# I2C_MULTIPLEX.net
KiCad netlist of a schematic drawn in Altium Designer
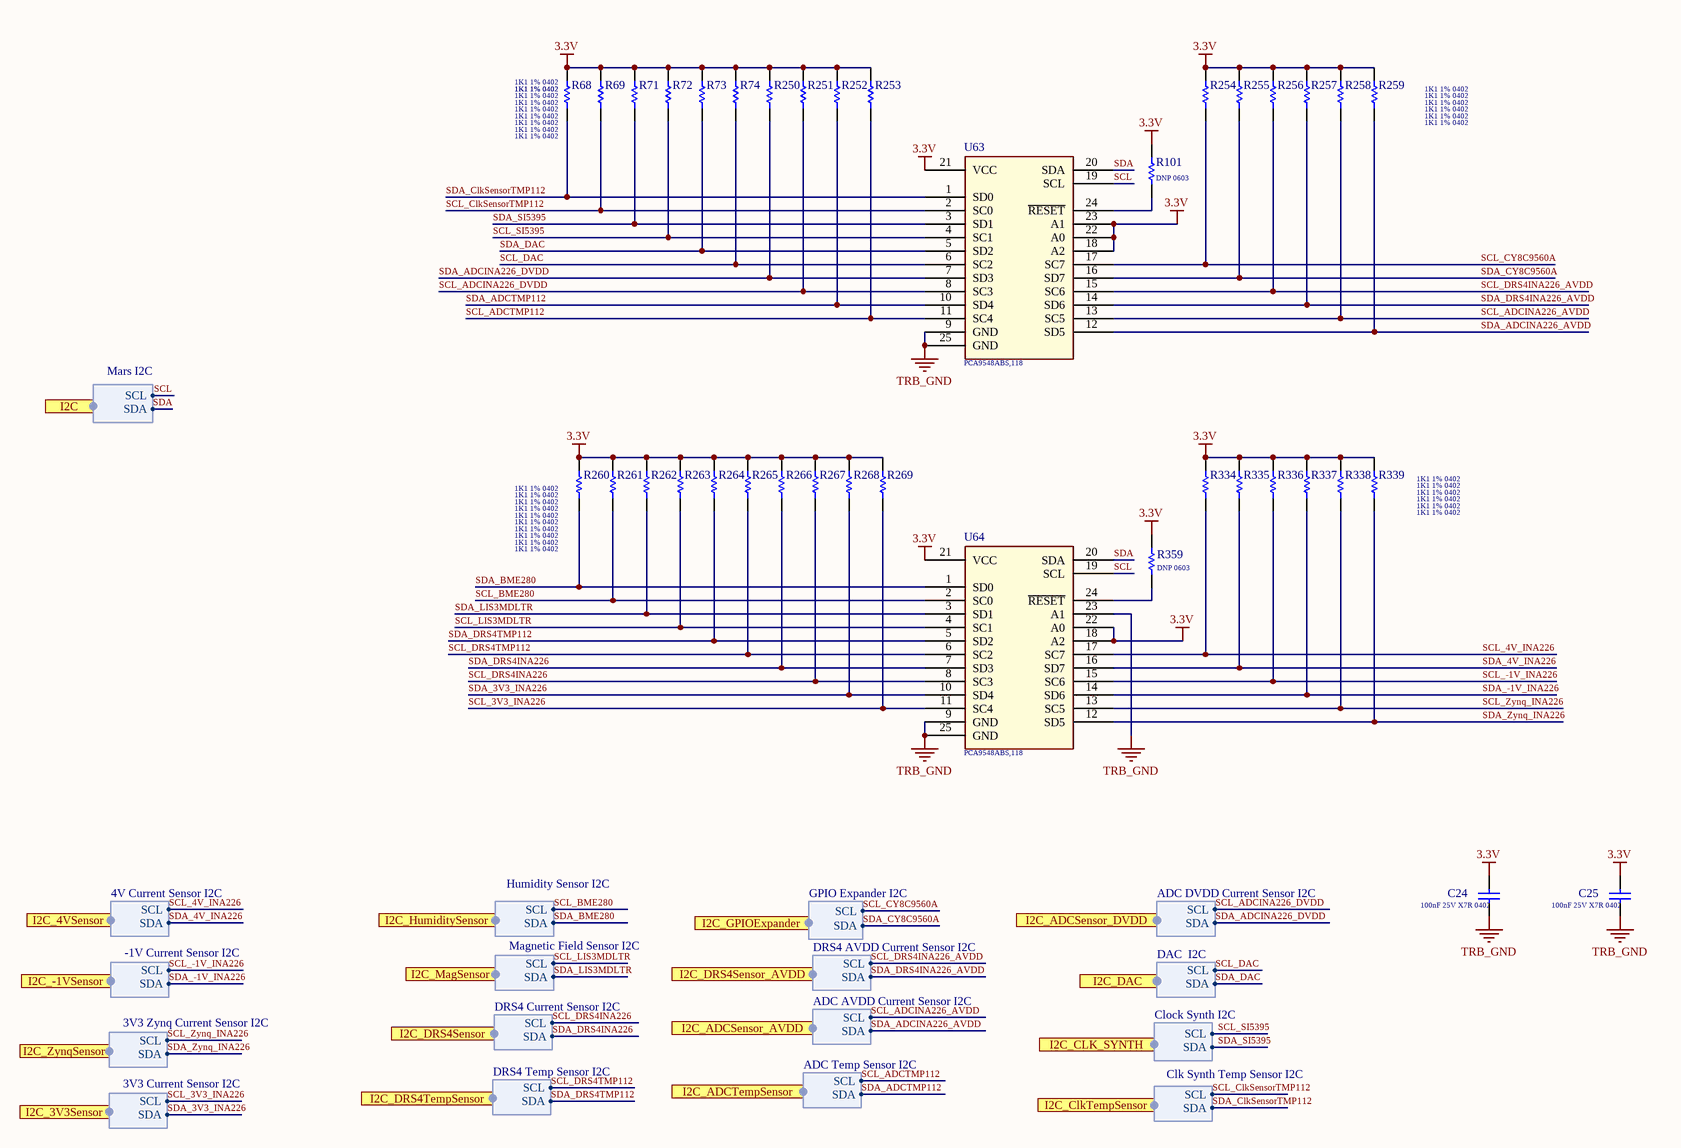
[diagram p0: I2C_MULTIPLEX.SchDoc]

(export (version "E")
  (design (tool "Eeschema 10.0.6"))
  (components
    (comp (ref "C24")
      (value "Cap_Taiyo_Yuden_TMK105B7104KV-FR_100nF")
      (footprint "Cap_Taiyo_Yuden_TMK105B7104KV-FR_100nF")
      (description "CAP CER 100nF 25V X7R 0402")
      (fields (field (name "CAPACITANCE") "100nF 25V X7R 0402"))
      (libsource (lib "Cap_Taiyo_Yuden_TMK105B7104KV-FR_100nF") (part "Cap_Taiyo_Yuden_TMK105B7104KV-FR_100nF"))
    )
    (comp (ref "C25")
      (value "Cap_Taiyo_Yuden_TMK105B7104KV-FR_100nF")
      (footprint "Cap_Taiyo_Yuden_TMK105B7104KV-FR_100nF")
      (description "CAP CER 100nF 25V X7R 0402")
      (fields (field (name "CAPACITANCE") "100nF 25V X7R 0402"))
      (libsource (lib "Cap_Taiyo_Yuden_TMK105B7104KV-FR_100nF") (part "Cap_Taiyo_Yuden_TMK105B7104KV-FR_100nF"))
    )
    (comp (ref "R68")
      (value "1K1 1% 0402")
      (footprint "RESC0402(1005)_L")
      (description "1K1 0.063W 1% 0402 (1005 Metric)  SMD")
      (fields (field (name "POWER") "0.063 W") (field (name "TOLERANCE") "1 %"))
      (libsource (lib "Altium Content Vault") (part "RES"))
    )
    (comp (ref "R69")
      (value "1K1 1% 0402")
      (footprint "RESC0402(1005)_L")
      (description "1K1 0.063W 1% 0402 (1005 Metric)  SMD")
      (fields (field (name "POWER") "0.063 W") (field (name "TOLERANCE") "1 %"))
      (libsource (lib "Altium Content Vault") (part "RES"))
    )
    (comp (ref "R71")
      (value "1K1 1% 0402")
      (footprint "RESC0402(1005)_L")
      (description "1K1 0.063W 1% 0402 (1005 Metric)  SMD")
      (fields (field (name "POWER") "0.063 W") (field (name "TOLERANCE") "1 %"))
      (libsource (lib "Altium Content Vault") (part "RES"))
    )
    (comp (ref "R72")
      (value "1K1 1% 0402")
      (footprint "RESC0402(1005)_L")
      (description "1K1 0.063W 1% 0402 (1005 Metric)  SMD")
      (fields (field (name "POWER") "0.063 W") (field (name "TOLERANCE") "1 %"))
      (libsource (lib "Altium Content Vault") (part "RES"))
    )
    (comp (ref "R73")
      (value "1K1 1% 0402")
      (footprint "RESC0402(1005)_L")
      (description "1K1 0.063W 1% 0402 (1005 Metric)  SMD")
      (fields (field (name "POWER") "0.063 W") (field (name "TOLERANCE") "1 %"))
      (libsource (lib "Altium Content Vault") (part "RES"))
    )
    (comp (ref "R74")
      (value "1K1 1% 0402")
      (footprint "RESC0402(1005)_L")
      (description "1K1 0.063W 1% 0402 (1005 Metric)  SMD")
      (fields (field (name "POWER") "0.063 W") (field (name "TOLERANCE") "1 %"))
      (libsource (lib "Altium Content Vault") (part "RES"))
    )
    (comp (ref "R101")
      (value "RES_DNP_0603")
      (footprint "RES_DNP_0603")
      (description "0603 Do not place resistor")
      (fields (field (name "RESISTANCE") "DNP 0603"))
      (libsource (lib "RES_DNP_0603") (part "RES_DNP_0603"))
    )
    (comp (ref "R250")
      (value "1K1 1% 0402")
      (footprint "RESC0402(1005)_L")
      (description "1K1 0.063W 1% 0402 (1005 Metric)  SMD")
      (fields (field (name "POWER") "0.063 W") (field (name "TOLERANCE") "1 %"))
      (libsource (lib "Altium Content Vault") (part "RES"))
    )
    (comp (ref "R251")
      (value "1K1 1% 0402")
      (footprint "RESC0402(1005)_L")
      (description "1K1 0.063W 1% 0402 (1005 Metric)  SMD")
      (fields (field (name "POWER") "0.063 W") (field (name "TOLERANCE") "1 %"))
      (libsource (lib "Altium Content Vault") (part "RES"))
    )
    (comp (ref "R252")
      (value "1K1 1% 0402")
      (footprint "RESC0402(1005)_L")
      (description "1K1 0.063W 1% 0402 (1005 Metric)  SMD")
      (fields (field (name "POWER") "0.063 W") (field (name "TOLERANCE") "1 %"))
      (libsource (lib "Altium Content Vault") (part "RES"))
    )
    (comp (ref "R253")
      (value "1K1 1% 0402")
      (footprint "RESC0402(1005)_L")
      (description "1K1 0.063W 1% 0402 (1005 Metric)  SMD")
      (fields (field (name "POWER") "0.063 W") (field (name "TOLERANCE") "1 %"))
      (libsource (lib "Altium Content Vault") (part "RES"))
    )
    (comp (ref "R254")
      (value "1K1 1% 0402")
      (footprint "RESC0402(1005)_L")
      (description "1K1 0.063W 1% 0402 (1005 Metric)  SMD")
      (fields (field (name "POWER") "0.063 W") (field (name "TOLERANCE") "1 %"))
      (libsource (lib "Altium Content Vault") (part "RES"))
    )
    (comp (ref "R255")
      (value "1K1 1% 0402")
      (footprint "RESC0402(1005)_L")
      (description "1K1 0.063W 1% 0402 (1005 Metric)  SMD")
      (fields (field (name "POWER") "0.063 W") (field (name "TOLERANCE") "1 %"))
      (libsource (lib "Altium Content Vault") (part "RES"))
    )
    (comp (ref "R256")
      (value "1K1 1% 0402")
      (footprint "RESC0402(1005)_L")
      (description "1K1 0.063W 1% 0402 (1005 Metric)  SMD")
      (fields (field (name "POWER") "0.063 W") (field (name "TOLERANCE") "1 %"))
      (libsource (lib "Altium Content Vault") (part "RES"))
    )
    (comp (ref "R257")
      (value "1K1 1% 0402")
      (footprint "RESC0402(1005)_L")
      (description "1K1 0.063W 1% 0402 (1005 Metric)  SMD")
      (fields (field (name "POWER") "0.063 W") (field (name "TOLERANCE") "1 %"))
      (libsource (lib "Altium Content Vault") (part "RES"))
    )
    (comp (ref "R258")
      (value "1K1 1% 0402")
      (footprint "RESC0402(1005)_L")
      (description "1K1 0.063W 1% 0402 (1005 Metric)  SMD")
      (fields (field (name "POWER") "0.063 W") (field (name "TOLERANCE") "1 %"))
      (libsource (lib "Altium Content Vault") (part "RES"))
    )
    (comp (ref "R259")
      (value "1K1 1% 0402")
      (footprint "RESC0402(1005)_L")
      (description "1K1 0.063W 1% 0402 (1005 Metric)  SMD")
      (fields (field (name "POWER") "0.063 W") (field (name "TOLERANCE") "1 %"))
      (libsource (lib "Altium Content Vault") (part "RES"))
    )
    (comp (ref "R260")
      (value "1K1 1% 0402")
      (footprint "RESC0402(1005)_L")
      (description "1K1 0.063W 1% 0402 (1005 Metric)  SMD")
      (fields (field (name "POWER") "0.063 W") (field (name "TOLERANCE") "1 %"))
      (libsource (lib "Altium Content Vault") (part "RES"))
    )
    (comp (ref "R261")
      (value "1K1 1% 0402")
      (footprint "RESC0402(1005)_L")
      (description "1K1 0.063W 1% 0402 (1005 Metric)  SMD")
      (fields (field (name "POWER") "0.063 W") (field (name "TOLERANCE") "1 %"))
      (libsource (lib "Altium Content Vault") (part "RES"))
    )
    (comp (ref "R262")
      (value "1K1 1% 0402")
      (footprint "RESC0402(1005)_L")
      (description "1K1 0.063W 1% 0402 (1005 Metric)  SMD")
      (fields (field (name "POWER") "0.063 W") (field (name "TOLERANCE") "1 %"))
      (libsource (lib "Altium Content Vault") (part "RES"))
    )
    (comp (ref "R263")
      (value "1K1 1% 0402")
      (footprint "RESC0402(1005)_L")
      (description "1K1 0.063W 1% 0402 (1005 Metric)  SMD")
      (fields (field (name "POWER") "0.063 W") (field (name "TOLERANCE") "1 %"))
      (libsource (lib "Altium Content Vault") (part "RES"))
    )
    (comp (ref "R264")
      (value "1K1 1% 0402")
      (footprint "RESC0402(1005)_L")
      (description "1K1 0.063W 1% 0402 (1005 Metric)  SMD")
      (fields (field (name "POWER") "0.063 W") (field (name "TOLERANCE") "1 %"))
      (libsource (lib "Altium Content Vault") (part "RES"))
    )
    (comp (ref "R265")
      (value "1K1 1% 0402")
      (footprint "RESC0402(1005)_L")
      (description "1K1 0.063W 1% 0402 (1005 Metric)  SMD")
      (fields (field (name "POWER") "0.063 W") (field (name "TOLERANCE") "1 %"))
      (libsource (lib "Altium Content Vault") (part "RES"))
    )
    (comp (ref "R266")
      (value "1K1 1% 0402")
      (footprint "RESC0402(1005)_L")
      (description "1K1 0.063W 1% 0402 (1005 Metric)  SMD")
      (fields (field (name "POWER") "0.063 W") (field (name "TOLERANCE") "1 %"))
      (libsource (lib "Altium Content Vault") (part "RES"))
    )
    (comp (ref "R267")
      (value "1K1 1% 0402")
      (footprint "RESC0402(1005)_L")
      (description "1K1 0.063W 1% 0402 (1005 Metric)  SMD")
      (fields (field (name "POWER") "0.063 W") (field (name "TOLERANCE") "1 %"))
      (libsource (lib "Altium Content Vault") (part "RES"))
    )
    (comp (ref "R268")
      (value "1K1 1% 0402")
      (footprint "RESC0402(1005)_L")
      (description "1K1 0.063W 1% 0402 (1005 Metric)  SMD")
      (fields (field (name "POWER") "0.063 W") (field (name "TOLERANCE") "1 %"))
      (libsource (lib "Altium Content Vault") (part "RES"))
    )
    (comp (ref "R269")
      (value "1K1 1% 0402")
      (footprint "RESC0402(1005)_L")
      (description "1K1 0.063W 1% 0402 (1005 Metric)  SMD")
      (fields (field (name "POWER") "0.063 W") (field (name "TOLERANCE") "1 %"))
      (libsource (lib "Altium Content Vault") (part "RES"))
    )
    (comp (ref "R334")
      (value "1K1 1% 0402")
      (footprint "RESC0402(1005)_L")
      (description "1K1 0.063W 1% 0402 (1005 Metric)  SMD")
      (fields (field (name "POWER") "0.063 W") (field (name "TOLERANCE") "1 %"))
      (libsource (lib "Altium Content Vault") (part "RES"))
    )
    (comp (ref "R335")
      (value "1K1 1% 0402")
      (footprint "RESC0402(1005)_L")
      (description "1K1 0.063W 1% 0402 (1005 Metric)  SMD")
      (fields (field (name "POWER") "0.063 W") (field (name "TOLERANCE") "1 %"))
      (libsource (lib "Altium Content Vault") (part "RES"))
    )
    (comp (ref "R336")
      (value "1K1 1% 0402")
      (footprint "RESC0402(1005)_L")
      (description "1K1 0.063W 1% 0402 (1005 Metric)  SMD")
      (fields (field (name "POWER") "0.063 W") (field (name "TOLERANCE") "1 %"))
      (libsource (lib "Altium Content Vault") (part "RES"))
    )
    (comp (ref "R337")
      (value "1K1 1% 0402")
      (footprint "RESC0402(1005)_L")
      (description "1K1 0.063W 1% 0402 (1005 Metric)  SMD")
      (fields (field (name "POWER") "0.063 W") (field (name "TOLERANCE") "1 %"))
      (libsource (lib "Altium Content Vault") (part "RES"))
    )
    (comp (ref "R338")
      (value "1K1 1% 0402")
      (footprint "RESC0402(1005)_L")
      (description "1K1 0.063W 1% 0402 (1005 Metric)  SMD")
      (fields (field (name "POWER") "0.063 W") (field (name "TOLERANCE") "1 %"))
      (libsource (lib "Altium Content Vault") (part "RES"))
    )
    (comp (ref "R339")
      (value "1K1 1% 0402")
      (footprint "RESC0402(1005)_L")
      (description "1K1 0.063W 1% 0402 (1005 Metric)  SMD")
      (fields (field (name "POWER") "0.063 W") (field (name "TOLERANCE") "1 %"))
      (libsource (lib "Altium Content Vault") (part "RES"))
    )
    (comp (ref "R359")
      (value "RES_DNP_0603")
      (footprint "RES_DNP_0603")
      (description "0603 Do not place resistor")
      (fields (field (name "RESISTANCE") "DNP 0603"))
      (libsource (lib "RES_DNP_0603") (part "RES_DNP_0603"))
    )
    (comp (ref "U63")
      (value "IC_NXP_PCA9548ABS,118_I2C_8Channel")
      (footprint "IC_NXP_PCA9548ABS,118_I2C_8Channel")
      (description "Multiplexer Switch ICs 8CH I2C SWTCH W/REST")
      (fields (field (name "SERIES") "PCA9548ABS,118"))
      (libsource (lib "IC_NXP_PCA9548ABS,118_I2C_8Channel") (part "IC_NXP_PCA9548ABS,118_I2C_8Channel"))
    )
    (comp (ref "U64")
      (value "IC_NXP_PCA9548ABS,118_I2C_8Channel")
      (footprint "IC_NXP_PCA9548ABS,118_I2C_8Channel")
      (description "Multiplexer Switch ICs 8CH I2C SWTCH W/REST")
      (fields (field (name "SERIES") "PCA9548ABS,118"))
      (libsource (lib "IC_NXP_PCA9548ABS,118_I2C_8Channel") (part "IC_NXP_PCA9548ABS,118_I2C_8Channel"))
    )
  )
  (nets
    (net (code "23") (name "/SCL") (class "Default")
      (node (ref "U63") (pin "19") (pinfunction "SCL_19") (pintype "passive"))
      (node (ref "U64") (pin "19") (pinfunction "SCL_19") (pintype "passive"))
    )
    (net (code "24") (name "/SCL_-1V_INA226") (class "Default")
      (node (ref "R336") (pin "1") (pinfunction "1_1") (pintype "passive"))
      (node (ref "U64") (pin "15") (pinfunction "SC6_15") (pintype "passive"))
    )
    (net (code "25") (name "/SCL_3V3_INA226") (class "Default")
      (node (ref "R269") (pin "1") (pinfunction "1_1") (pintype "passive"))
      (node (ref "U64") (pin "11") (pinfunction "SC4_11") (pintype "passive"))
    )
    (net (code "26") (name "/SCL_4V_INA226") (class "Default")
      (node (ref "R334") (pin "1") (pinfunction "1_1") (pintype "passive"))
      (node (ref "U64") (pin "17") (pinfunction "SC7_17") (pintype "passive"))
    )
    (net (code "27") (name "/SCL_ADCINA226_AVDD") (class "Default")
      (node (ref "R258") (pin "1") (pinfunction "1_1") (pintype "passive"))
      (node (ref "U63") (pin "13") (pinfunction "SC5_13") (pintype "passive"))
    )
    (net (code "28") (name "/SCL_ADCINA226_DVDD") (class "Default")
      (node (ref "R251") (pin "1") (pinfunction "1_1") (pintype "passive"))
      (node (ref "U63") (pin "8") (pinfunction "SC3_8") (pintype "passive"))
    )
    (net (code "29") (name "/SCL_ADCTMP112") (class "Default")
      (node (ref "R253") (pin "1") (pinfunction "1_1") (pintype "passive"))
      (node (ref "U63") (pin "11") (pinfunction "SC4_11") (pintype "passive"))
    )
    (net (code "30") (name "/SCL_BME280") (class "Default")
      (node (ref "R261") (pin "1") (pinfunction "1_1") (pintype "passive"))
      (node (ref "U64") (pin "2") (pinfunction "SC0_2") (pintype "passive"))
    )
    (net (code "31") (name "/SCL_CY8C9560A") (class "Default")
      (node (ref "R254") (pin "1") (pinfunction "1_1") (pintype "passive"))
      (node (ref "U63") (pin "17") (pinfunction "SC7_17") (pintype "passive"))
    )
    (net (code "32") (name "/SCL_ClkSensorTMP112") (class "Default")
      (node (ref "R69") (pin "1") (pinfunction "1_1") (pintype "passive"))
      (node (ref "U63") (pin "2") (pinfunction "SC0_2") (pintype "passive"))
    )
    (net (code "33") (name "/SCL_DAC") (class "Default")
      (node (ref "R74") (pin "1") (pinfunction "1_1") (pintype "passive"))
      (node (ref "U63") (pin "6") (pinfunction "SC2_6") (pintype "passive"))
    )
    (net (code "34") (name "/SCL_DRS4INA226") (class "Default")
      (node (ref "R267") (pin "1") (pinfunction "1_1") (pintype "passive"))
      (node (ref "U64") (pin "8") (pinfunction "SC3_8") (pintype "passive"))
    )
    (net (code "35") (name "/SCL_DRS4INA226_AVDD") (class "Default")
      (node (ref "R256") (pin "1") (pinfunction "1_1") (pintype "passive"))
      (node (ref "U63") (pin "15") (pinfunction "SC6_15") (pintype "passive"))
    )
    (net (code "36") (name "/SCL_DRS4TMP112") (class "Default")
      (node (ref "R265") (pin "1") (pinfunction "1_1") (pintype "passive"))
      (node (ref "U64") (pin "6") (pinfunction "SC2_6") (pintype "passive"))
    )
    (net (code "37") (name "/SCL_LIS3MDLTR") (class "Default")
      (node (ref "R263") (pin "1") (pinfunction "1_1") (pintype "passive"))
      (node (ref "U64") (pin "4") (pinfunction "SC1_4") (pintype "passive"))
    )
    (net (code "38") (name "/SCL_SI5395") (class "Default")
      (node (ref "R72") (pin "1") (pinfunction "1_1") (pintype "passive"))
      (node (ref "U63") (pin "4") (pinfunction "SC1_4") (pintype "passive"))
    )
    (net (code "39") (name "/SCL_Zynq_INA226") (class "Default")
      (node (ref "R338") (pin "1") (pinfunction "1_1") (pintype "passive"))
      (node (ref "U64") (pin "13") (pinfunction "SC5_13") (pintype "passive"))
    )
    (net (code "40") (name "/SDA") (class "Default")
      (node (ref "U63") (pin "20") (pinfunction "SDA_20") (pintype "passive"))
      (node (ref "U64") (pin "20") (pinfunction "SDA_20") (pintype "passive"))
    )
    (net (code "41") (name "/SDA_-1V_INA226") (class "Default")
      (node (ref "R337") (pin "1") (pinfunction "1_1") (pintype "passive"))
      (node (ref "U64") (pin "14") (pinfunction "SD6_14") (pintype "passive"))
    )
    (net (code "42") (name "/SDA_3V3_INA226") (class "Default")
      (node (ref "R268") (pin "1") (pinfunction "1_1") (pintype "passive"))
      (node (ref "U64") (pin "10") (pinfunction "SD4_10") (pintype "passive"))
    )
    (net (code "43") (name "/SDA_4V_INA226") (class "Default")
      (node (ref "R335") (pin "1") (pinfunction "1_1") (pintype "passive"))
      (node (ref "U64") (pin "16") (pinfunction "SD7_16") (pintype "passive"))
    )
    (net (code "44") (name "/SDA_ADCINA226_AVDD") (class "Default")
      (node (ref "R259") (pin "1") (pinfunction "1_1") (pintype "passive"))
      (node (ref "U63") (pin "12") (pinfunction "SD5_12") (pintype "passive"))
    )
    (net (code "45") (name "/SDA_ADCINA226_DVDD") (class "Default")
      (node (ref "R250") (pin "1") (pinfunction "1_1") (pintype "passive"))
      (node (ref "U63") (pin "7") (pinfunction "SD3_7") (pintype "passive"))
    )
    (net (code "46") (name "/SDA_ADCTMP112") (class "Default")
      (node (ref "R252") (pin "1") (pinfunction "1_1") (pintype "passive"))
      (node (ref "U63") (pin "10") (pinfunction "SD4_10") (pintype "passive"))
    )
    (net (code "47") (name "/SDA_BME280") (class "Default")
      (node (ref "R260") (pin "1") (pinfunction "1_1") (pintype "passive"))
      (node (ref "U64") (pin "1") (pinfunction "SD0_1") (pintype "passive"))
    )
    (net (code "48") (name "/SDA_CY8C9560A") (class "Default")
      (node (ref "R255") (pin "1") (pinfunction "1_1") (pintype "passive"))
      (node (ref "U63") (pin "16") (pinfunction "SD7_16") (pintype "passive"))
    )
    (net (code "49") (name "/SDA_ClkSensorTMP112") (class "Default")
      (node (ref "R68") (pin "1") (pinfunction "1_1") (pintype "passive"))
      (node (ref "U63") (pin "1") (pinfunction "SD0_1") (pintype "passive"))
    )
    (net (code "50") (name "/SDA_DAC") (class "Default")
      (node (ref "R73") (pin "1") (pinfunction "1_1") (pintype "passive"))
      (node (ref "U63") (pin "5") (pinfunction "SD2_5") (pintype "passive"))
    )
    (net (code "51") (name "/SDA_DRS4INA226") (class "Default")
      (node (ref "R266") (pin "1") (pinfunction "1_1") (pintype "passive"))
      (node (ref "U64") (pin "7") (pinfunction "SD3_7") (pintype "passive"))
    )
    (net (code "52") (name "/SDA_DRS4INA226_AVDD") (class "Default")
      (node (ref "R257") (pin "1") (pinfunction "1_1") (pintype "passive"))
      (node (ref "U63") (pin "14") (pinfunction "SD6_14") (pintype "passive"))
    )
    (net (code "53") (name "/SDA_DRS4TMP112") (class "Default")
      (node (ref "R264") (pin "1") (pinfunction "1_1") (pintype "passive"))
      (node (ref "U64") (pin "5") (pinfunction "SD2_5") (pintype "passive"))
    )
    (net (code "54") (name "/SDA_LIS3MDLTR") (class "Default")
      (node (ref "R262") (pin "1") (pinfunction "1_1") (pintype "passive"))
      (node (ref "U64") (pin "3") (pinfunction "SD1_3") (pintype "passive"))
    )
    (net (code "55") (name "/SDA_SI5395") (class "Default")
      (node (ref "R71") (pin "1") (pinfunction "1_1") (pintype "passive"))
      (node (ref "U63") (pin "3") (pinfunction "SD1_3") (pintype "passive"))
    )
    (net (code "56") (name "/SDA_Zynq_INA226") (class "Default")
      (node (ref "R339") (pin "1") (pinfunction "1_1") (pintype "passive"))
      (node (ref "U64") (pin "12") (pinfunction "SD5_12") (pintype "passive"))
    )
    (net (code "74") (name "3.3V") (class "Default")
      (node (ref "C24") (pin "2") (pinfunction "2_2") (pintype "passive"))
      (node (ref "C25") (pin "2") (pinfunction "2_2") (pintype "passive"))
      (node (ref "R101") (pin "1") (pinfunction "1_1") (pintype "passive"))
      (node (ref "R250") (pin "2") (pinfunction "2_2") (pintype "passive"))
      (node (ref "R251") (pin "2") (pinfunction "2_2") (pintype "passive"))
      (node (ref "R252") (pin "2") (pinfunction "2_2") (pintype "passive"))
      (node (ref "R253") (pin "2") (pinfunction "2_2") (pintype "passive"))
      (node (ref "R254") (pin "2") (pinfunction "2_2") (pintype "passive"))
      (node (ref "R255") (pin "2") (pinfunction "2_2") (pintype "passive"))
      (node (ref "R256") (pin "2") (pinfunction "2_2") (pintype "passive"))
      (node (ref "R257") (pin "2") (pinfunction "2_2") (pintype "passive"))
      (node (ref "R258") (pin "2") (pinfunction "2_2") (pintype "passive"))
      (node (ref "R259") (pin "2") (pinfunction "2_2") (pintype "passive"))
      (node (ref "R260") (pin "2") (pinfunction "2_2") (pintype "passive"))
      (node (ref "R261") (pin "2") (pinfunction "2_2") (pintype "passive"))
      (node (ref "R262") (pin "2") (pinfunction "2_2") (pintype "passive"))
      (node (ref "R263") (pin "2") (pinfunction "2_2") (pintype "passive"))
      (node (ref "R264") (pin "2") (pinfunction "2_2") (pintype "passive"))
      (node (ref "R265") (pin "2") (pinfunction "2_2") (pintype "passive"))
      (node (ref "R266") (pin "2") (pinfunction "2_2") (pintype "passive"))
      (node (ref "R267") (pin "2") (pinfunction "2_2") (pintype "passive"))
      (node (ref "R268") (pin "2") (pinfunction "2_2") (pintype "passive"))
      (node (ref "R269") (pin "2") (pinfunction "2_2") (pintype "passive"))
      (node (ref "R334") (pin "2") (pinfunction "2_2") (pintype "passive"))
      (node (ref "R335") (pin "2") (pinfunction "2_2") (pintype "passive"))
      (node (ref "R336") (pin "2") (pinfunction "2_2") (pintype "passive"))
      (node (ref "R337") (pin "2") (pinfunction "2_2") (pintype "passive"))
      (node (ref "R338") (pin "2") (pinfunction "2_2") (pintype "passive"))
      (node (ref "R339") (pin "2") (pinfunction "2_2") (pintype "passive"))
      (node (ref "R359") (pin "1") (pinfunction "1_1") (pintype "passive"))
      (node (ref "R68") (pin "2") (pinfunction "2_2") (pintype "passive"))
      (node (ref "R69") (pin "2") (pinfunction "2_2") (pintype "passive"))
      (node (ref "R71") (pin "2") (pinfunction "2_2") (pintype "passive"))
      (node (ref "R72") (pin "2") (pinfunction "2_2") (pintype "passive"))
      (node (ref "R73") (pin "2") (pinfunction "2_2") (pintype "passive"))
      (node (ref "R74") (pin "2") (pinfunction "2_2") (pintype "passive"))
      (node (ref "U63") (pin "18") (pinfunction "A2_18") (pintype "passive"))
      (node (ref "U63") (pin "21") (pinfunction "VCC_21") (pintype "passive"))
      (node (ref "U63") (pin "22") (pinfunction "A0_22") (pintype "passive"))
      (node (ref "U63") (pin "23") (pinfunction "A1_23") (pintype "passive"))
      (node (ref "U64") (pin "18") (pinfunction "A2_18") (pintype "passive"))
      (node (ref "U64") (pin "21") (pinfunction "VCC_21") (pintype "passive"))
      (node (ref "U64") (pin "22") (pinfunction "A0_22") (pintype "passive"))
    )
    (net (code "75") (name "Net-(U63-~{RESET})") (class "Default")
      (node (ref "R101") (pin "2") (pinfunction "2_2") (pintype "passive"))
      (node (ref "U63") (pin "24") (pinfunction "~{RESET}_24") (pintype "passive"))
    )
    (net (code "76") (name "Net-(U64-~{RESET})") (class "Default")
      (node (ref "R359") (pin "2") (pinfunction "2_2") (pintype "passive"))
      (node (ref "U64") (pin "24") (pinfunction "~{RESET}_24") (pintype "passive"))
    )
    (net (code "77") (name "TRB_GND") (class "Default")
      (node (ref "C24") (pin "1") (pinfunction "1_1") (pintype "passive"))
      (node (ref "C25") (pin "1") (pinfunction "1_1") (pintype "passive"))
      (node (ref "U63") (pin "25") (pinfunction "GND_25") (pintype "passive"))
      (node (ref "U63") (pin "9") (pinfunction "GND_9") (pintype "passive"))
      (node (ref "U64") (pin "23") (pinfunction "A1_23") (pintype "passive"))
      (node (ref "U64") (pin "25") (pinfunction "GND_25") (pintype "passive"))
      (node (ref "U64") (pin "9") (pinfunction "GND_9") (pintype "passive"))
    )
  )
)
